# caudalimetro.net
KiCad netlist of a schematic drawn in EAGLE
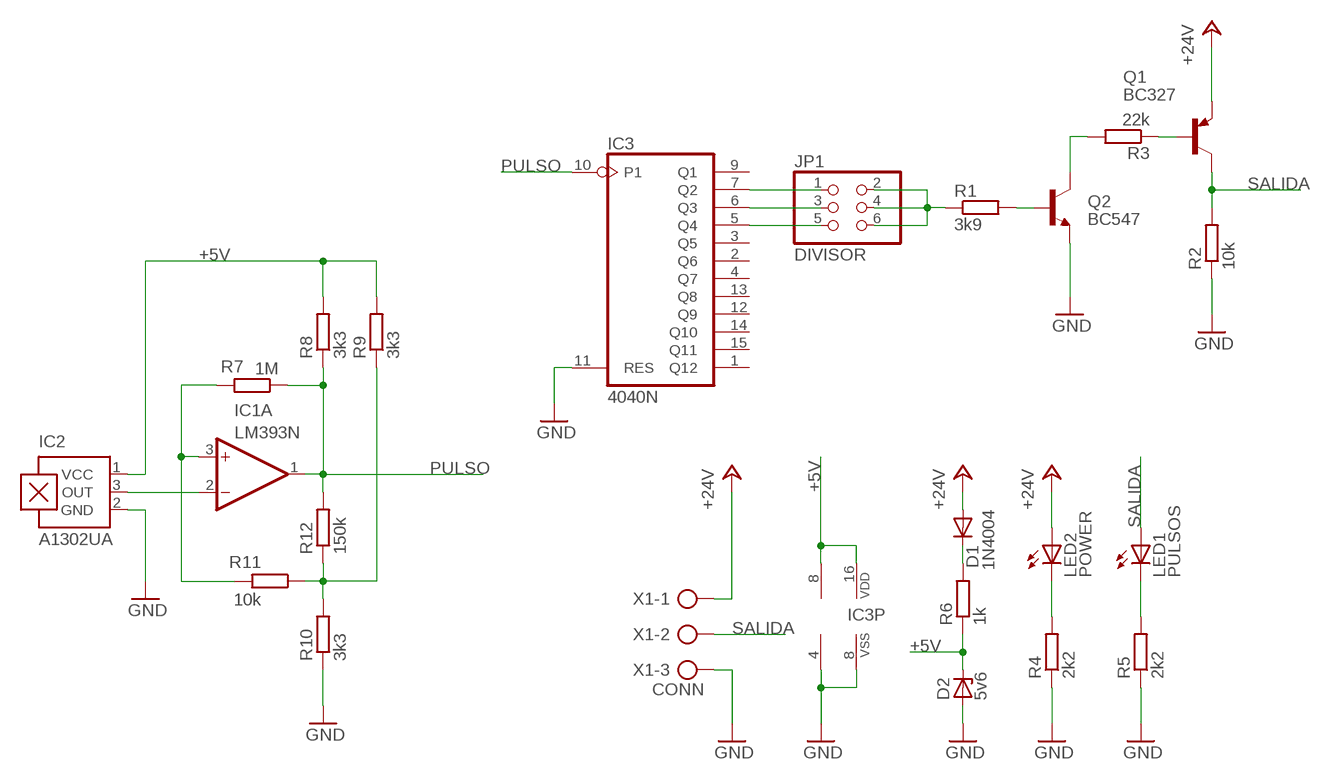
[diagram p0: schematic, sheet 1]

(export (version "E")
  (design (tool "Eeschema 10.0.6"))
  (components
    (comp (ref "D1")
      (value "1N4004")
      (footprint "eagle-import:DO41-10")
      (libsource (lib "eagle-import") (part "1N4004"))
    )
    (comp (ref "D2")
      (value "5v6")
      (footprint "eagle-import:ZDIO-2.5")
      (libsource (lib "eagle-import") (part "ZENER-DIODEZD-2.5"))
    )
    (comp (ref "IC1")
      (value "LM393N")
      (footprint "eagle-import:DIL08")
      (libsource (lib "eagle-import") (part "LM393N"))
    )
    (comp (ref "IC2")
      (value "A1302UA")
      (footprint "eagle-import:SIP3-UA")
      (fields (field (name "MF") "ALLEGRO MICROSYSTEMS, INC.") (field (name "MPN") "A1302EUA-T"))
      (libsource (lib "eagle-import") (part "A13?UA02"))
    )
    (comp (ref "IC3")
      (value "4040N")
      (footprint "eagle-import:DIL16")
      (libsource (lib "eagle-import") (part "4040N"))
    )
    (comp (ref "JP1")
      (value "DIVISOR")
      (footprint "eagle-import:2X03")
      (libsource (lib "eagle-import") (part "PINHD-2X3"))
    )
    (comp (ref "LED1")
      (value "PULSOS")
      (footprint "eagle-import:LED3MM")
      (libsource (lib "eagle-import") (part "LED3MM"))
    )
    (comp (ref "LED2")
      (value "POWER")
      (footprint "eagle-import:LED3MM")
      (libsource (lib "eagle-import") (part "LED3MM"))
    )
    (comp (ref "Q1")
      (value "BC327")
      (footprint "eagle-import:TO92")
      (libsource (lib "eagle-import") (part "BC327"))
    )
    (comp (ref "Q2")
      (value "BC547")
      (footprint "eagle-import:TO92")
      (libsource (lib "eagle-import") (part "BC547"))
    )
    (comp (ref "R1")
      (value "3k9")
      (footprint "eagle-import:0207_2V")
      (libsource (lib "eagle-import") (part "R-EU_0207/2V"))
    )
    (comp (ref "R2")
      (value "10k")
      (footprint "eagle-import:0207_2V")
      (libsource (lib "eagle-import") (part "R-EU_0207/2V"))
    )
    (comp (ref "R3")
      (value "22k")
      (footprint "eagle-import:0207_2V")
      (libsource (lib "eagle-import") (part "R-EU_0207/2V"))
    )
    (comp (ref "R4")
      (value "2k2")
      (footprint "eagle-import:0207_2V")
      (libsource (lib "eagle-import") (part "R-EU_0207/2V"))
    )
    (comp (ref "R5")
      (value "2k2")
      (footprint "eagle-import:0207_2V")
      (libsource (lib "eagle-import") (part "R-EU_0207/2V"))
    )
    (comp (ref "R6")
      (value "1k")
      (footprint "eagle-import:0207_2V")
      (libsource (lib "eagle-import") (part "R-EU_0207/2V"))
    )
    (comp (ref "R7")
      (value "1M")
      (footprint "eagle-import:0207_2V")
      (libsource (lib "eagle-import") (part "R-EU_0207/2V"))
    )
    (comp (ref "R8")
      (value "3k3")
      (footprint "eagle-import:0207_2V")
      (libsource (lib "eagle-import") (part "R-EU_0207/2V"))
    )
    (comp (ref "R9")
      (value "3k3")
      (footprint "eagle-import:0207_2V")
      (libsource (lib "eagle-import") (part "R-EU_0207/2V"))
    )
    (comp (ref "R10")
      (value "3k3")
      (footprint "eagle-import:0207_2V")
      (libsource (lib "eagle-import") (part "R-EU_0207/2V"))
    )
    (comp (ref "R11")
      (value "10k")
      (footprint "eagle-import:0207_2V")
      (libsource (lib "eagle-import") (part "R-EU_0207/2V"))
    )
    (comp (ref "R12")
      (value "150k")
      (footprint "eagle-import:0207_2V")
      (libsource (lib "eagle-import") (part "R-EU_0207/2V"))
    )
    (comp (ref "X1")
      (value "CONN")
      (footprint "eagle-import:AK300_3")
      (libsource (lib "eagle-import") (part "AK300/3"))
    )
  )
  (nets
    (net (code "1") (name "+24V") (class "Default")
      (node (ref "D1") (pin "A") (pinfunction "A_A") (pintype "passive"))
      (node (ref "LED2") (pin "A") (pinfunction "A_A") (pintype "passive"))
      (node (ref "Q1") (pin "1") (pinfunction "E_1") (pintype "passive"))
      (node (ref "X1") (pin "1") (pinfunction "KL_1") (pintype "passive"))
    )
    (net (code "2") (name "/+5V") (class "Default")
      (node (ref "D2") (pin "C") (pinfunction "C_C") (pintype "passive"))
      (node (ref "IC1") (pin "8") (pinfunction "V+_8") (pintype "power_in"))
      (node (ref "IC2") (pin "1") (pinfunction "VCC_1") (pintype "power_in"))
      (node (ref "IC3") (pin "16") (pinfunction "VDD_16") (pintype "power_in"))
      (node (ref "R6") (pin "1") (pinfunction "1_1") (pintype "passive"))
      (node (ref "R8") (pin "2") (pinfunction "2_2") (pintype "passive"))
      (node (ref "R9") (pin "2") (pinfunction "2_2") (pintype "passive"))
    )
    (net (code "3") (name "/PULSO") (class "Default")
      (node (ref "IC1") (pin "1") (pinfunction "OUT_1") (pintype "output"))
      (node (ref "IC3") (pin "10") (pinfunction "P1_10") (pintype "input"))
      (node (ref "R12") (pin "2") (pinfunction "2_2") (pintype "passive"))
      (node (ref "R7") (pin "1") (pinfunction "1_1") (pintype "passive"))
      (node (ref "R8") (pin "1") (pinfunction "1_1") (pintype "passive"))
    )
    (net (code "4") (name "/SALIDA") (class "Default")
      (node (ref "LED1") (pin "A") (pinfunction "A_A") (pintype "passive"))
      (node (ref "Q1") (pin "3") (pinfunction "C_3") (pintype "passive"))
      (node (ref "R2") (pin "2") (pinfunction "2_2") (pintype "passive"))
      (node (ref "X1") (pin "2") (pinfunction "KL_2") (pintype "passive"))
    )
    (net (code "5") (name "GND") (class "Default")
      (node (ref "D2") (pin "A") (pinfunction "A_A") (pintype "passive"))
      (node (ref "IC1") (pin "4") (pinfunction "V-_4") (pintype "power_in"))
      (node (ref "IC2") (pin "2") (pinfunction "GND_2") (pintype "power_in"))
      (node (ref "IC3") (pin "11") (pinfunction "RES_11") (pintype "input"))
      (node (ref "IC3") (pin "8") (pinfunction "VSS_8") (pintype "power_in"))
      (node (ref "Q2") (pin "1") (pinfunction "E_1") (pintype "passive"))
      (node (ref "R10") (pin "1") (pinfunction "1_1") (pintype "passive"))
      (node (ref "R2") (pin "1") (pinfunction "1_1") (pintype "passive"))
      (node (ref "R4") (pin "1") (pinfunction "1_1") (pintype "passive"))
      (node (ref "R5") (pin "1") (pinfunction "1_1") (pintype "passive"))
      (node (ref "X1") (pin "3") (pinfunction "KL_3") (pintype "passive"))
    )
    (net (code "6") (name "Net-(D1-PadC)") (class "Default")
      (node (ref "D1") (pin "C") (pinfunction "C_C") (pintype "passive"))
      (node (ref "R6") (pin "2") (pinfunction "2_2") (pintype "passive"))
    )
    (net (code "7") (name "Net-(IC1A-+IN)") (class "Default")
      (node (ref "IC1") (pin "3") (pinfunction "+IN_3") (pintype "input"))
      (node (ref "R11") (pin "2") (pinfunction "2_2") (pintype "passive"))
      (node (ref "R7") (pin "2") (pinfunction "2_2") (pintype "passive"))
    )
    (net (code "8") (name "Net-(IC1A--IN)") (class "Default")
      (node (ref "IC1") (pin "2") (pinfunction "-IN_2") (pintype "input"))
      (node (ref "IC2") (pin "3") (pinfunction "OUT_3") (pintype "output"))
    )
    (net (code "9") (name "Net-(IC3A-Q2)") (class "Default")
      (node (ref "IC3") (pin "7") (pinfunction "Q2_7") (pintype "output"))
      (node (ref "JP1") (pin "1") (pinfunction "1_1") (pintype "passive"))
    )
    (net (code "10") (name "Net-(IC3A-Q3)") (class "Default")
      (node (ref "IC3") (pin "6") (pinfunction "Q3_6") (pintype "output"))
      (node (ref "JP1") (pin "3") (pinfunction "3_3") (pintype "passive"))
    )
    (net (code "11") (name "Net-(IC3A-Q4)") (class "Default")
      (node (ref "IC3") (pin "5") (pinfunction "Q4_5") (pintype "output"))
      (node (ref "JP1") (pin "5") (pinfunction "5_5") (pintype "passive"))
    )
    (net (code "12") (name "Net-(JP1-Pad2)") (class "Default")
      (node (ref "JP1") (pin "2") (pinfunction "2_2") (pintype "passive"))
      (node (ref "JP1") (pin "4") (pinfunction "4_4") (pintype "passive"))
      (node (ref "JP1") (pin "6") (pinfunction "6_6") (pintype "passive"))
      (node (ref "R1") (pin "1") (pinfunction "1_1") (pintype "passive"))
    )
    (net (code "13") (name "Net-(LED1-C)") (class "Default")
      (node (ref "LED1") (pin "K") (pinfunction "C_K") (pintype "passive"))
      (node (ref "R5") (pin "2") (pinfunction "2_2") (pintype "passive"))
    )
    (net (code "14") (name "Net-(LED2-C)") (class "Default")
      (node (ref "LED2") (pin "K") (pinfunction "C_K") (pintype "passive"))
      (node (ref "R4") (pin "2") (pinfunction "2_2") (pintype "passive"))
    )
    (net (code "15") (name "Net-(Q1-B)") (class "Default")
      (node (ref "Q1") (pin "2") (pinfunction "B_2") (pintype "passive"))
      (node (ref "R3") (pin "1") (pinfunction "1_1") (pintype "passive"))
    )
    (net (code "16") (name "Net-(Q2-B)") (class "Default")
      (node (ref "Q2") (pin "2") (pinfunction "B_2") (pintype "passive"))
      (node (ref "R1") (pin "2") (pinfunction "2_2") (pintype "passive"))
    )
    (net (code "17") (name "Net-(Q2-C)") (class "Default")
      (node (ref "Q2") (pin "3") (pinfunction "C_3") (pintype "passive"))
      (node (ref "R3") (pin "2") (pinfunction "2_2") (pintype "passive"))
    )
    (net (code "18") (name "Net-(R10-Pad2)") (class "Default")
      (node (ref "R10") (pin "2") (pinfunction "2_2") (pintype "passive"))
      (node (ref "R11") (pin "1") (pinfunction "1_1") (pintype "passive"))
      (node (ref "R12") (pin "1") (pinfunction "1_1") (pintype "passive"))
      (node (ref "R9") (pin "1") (pinfunction "1_1") (pintype "passive"))
    )
    (net (code "19") (name "unconnected-(IC3A-Q1-Pad9)") (class "Default")
      (node (ref "IC3") (pin "9") (pinfunction "Q1_9") (pintype "output"))
    )
    (net (code "20") (name "unconnected-(IC3A-Q5-Pad3)") (class "Default")
      (node (ref "IC3") (pin "3") (pinfunction "Q5_3") (pintype "output"))
    )
    (net (code "21") (name "unconnected-(IC3A-Q6-Pad2)") (class "Default")
      (node (ref "IC3") (pin "2") (pinfunction "Q6_2") (pintype "output"))
    )
    (net (code "22") (name "unconnected-(IC3A-Q7-Pad4)") (class "Default")
      (node (ref "IC3") (pin "4") (pinfunction "Q7_4") (pintype "output"))
    )
    (net (code "23") (name "unconnected-(IC3A-Q8-Pad13)") (class "Default")
      (node (ref "IC3") (pin "13") (pinfunction "Q8_13") (pintype "output"))
    )
    (net (code "24") (name "unconnected-(IC3A-Q9-Pad12)") (class "Default")
      (node (ref "IC3") (pin "12") (pinfunction "Q9_12") (pintype "output"))
    )
    (net (code "25") (name "unconnected-(IC3A-Q10-Pad14)") (class "Default")
      (node (ref "IC3") (pin "14") (pinfunction "Q10_14") (pintype "output"))
    )
    (net (code "26") (name "unconnected-(IC3A-Q11-Pad15)") (class "Default")
      (node (ref "IC3") (pin "15") (pinfunction "Q11_15") (pintype "output"))
    )
    (net (code "27") (name "unconnected-(IC3A-Q12-Pad1)") (class "Default")
      (node (ref "IC3") (pin "1") (pinfunction "Q12_1") (pintype "output"))
    )
  )
)
